# POWER_SUPPLY_PAIRED.net
KiCad netlist of a schematic drawn in Altium Designer
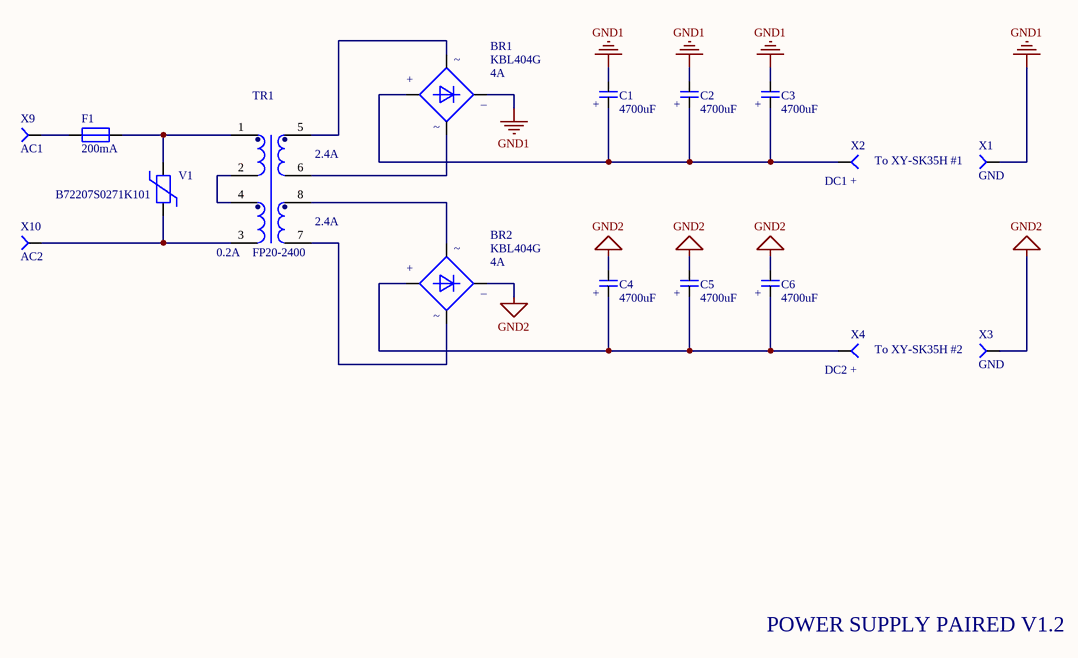
[diagram p0: POWER_SUPPLY_PAIRED.SchDoc]

(export (version "E")
  (design (tool "Eeschema 10.0.6"))
  (components
    (comp (ref "BR1")
      (value "KBL404G")
      (footprint "THT_BRIGDE_KBL404G")
      (description "THT Diode Bridge 400V 4A KBL404G TAIWAN SEMICONDUCTOR")
      (libsource (lib "THT_BRIGDE_KBL404G") (part "THT_BRIGDE_KBL404G"))
    )
    (comp (ref "BR2")
      (value "KBL404G")
      (footprint "THT_BRIGDE_KBL404G")
      (description "THT Diode Bridge 400V 4A KBL404G TAIWAN SEMICONDUCTOR")
      (libsource (lib "THT_BRIGDE_KBL404G") (part "THT_BRIGDE_KBL404G"))
    )
    (comp (ref "C1")
      (value "4700uF")
      (footprint "THT_CAP_EL_SAMXON_EKM478M1HL40RRSAP")
      (description "THT Capacitor Electrolytic 50V 4700uF Pitch 7.5mm SAMXON EKM478M1HL40RRSAP")
      (libsource (lib "THT_CAP_EL_SAMXON_EKM478M1HL40RRSAP") (part "THT_CAP_EL_SAMXON_EKM478M1HL40RRSAP"))
    )
    (comp (ref "C2")
      (value "4700uF")
      (footprint "THT_CAP_EL_SAMXON_EKM478M1HL40RRSAP")
      (description "THT Capacitor Electrolytic 50V 4700uF Pitch 7.5mm SAMXON EKM478M1HL40RRSAP")
      (libsource (lib "THT_CAP_EL_SAMXON_EKM478M1HL40RRSAP") (part "THT_CAP_EL_SAMXON_EKM478M1HL40RRSAP"))
    )
    (comp (ref "C3")
      (value "4700uF")
      (footprint "THT_CAP_EL_SAMXON_EKM478M1HL40RRSAP")
      (description "THT Capacitor Electrolytic 50V 4700uF Pitch 7.5mm SAMXON EKM478M1HL40RRSAP")
      (libsource (lib "THT_CAP_EL_SAMXON_EKM478M1HL40RRSAP") (part "THT_CAP_EL_SAMXON_EKM478M1HL40RRSAP"))
    )
    (comp (ref "C4")
      (value "4700uF")
      (footprint "THT_CAP_EL_SAMXON_EKM478M1HL40RRSAP")
      (description "THT Capacitor Electrolytic 50V 4700uF Pitch 7.5mm SAMXON EKM478M1HL40RRSAP")
      (libsource (lib "THT_CAP_EL_SAMXON_EKM478M1HL40RRSAP") (part "THT_CAP_EL_SAMXON_EKM478M1HL40RRSAP"))
    )
    (comp (ref "C5")
      (value "4700uF")
      (footprint "THT_CAP_EL_SAMXON_EKM478M1HL40RRSAP")
      (description "THT Capacitor Electrolytic 50V 4700uF Pitch 7.5mm SAMXON EKM478M1HL40RRSAP")
      (libsource (lib "THT_CAP_EL_SAMXON_EKM478M1HL40RRSAP") (part "THT_CAP_EL_SAMXON_EKM478M1HL40RRSAP"))
    )
    (comp (ref "C6")
      (value "4700uF")
      (footprint "THT_CAP_EL_SAMXON_EKM478M1HL40RRSAP")
      (description "THT Capacitor Electrolytic 50V 4700uF Pitch 7.5mm SAMXON EKM478M1HL40RRSAP")
      (libsource (lib "THT_CAP_EL_SAMXON_EKM478M1HL40RRSAP") (part "THT_CAP_EL_SAMXON_EKM478M1HL40RRSAP"))
    )
    (comp (ref "F1")
      (value "200mA")
      (footprint "THT_FUSE-MICRO_MTS0200A")
      (description "THT Fuse Slow Blow Micro Fuse, 250V/200mA REOMAX")
      (libsource (lib "THT_FUSE-MICRO_MTS0200A") (part "THT_FUSE-MICRO_MTS0200A"))
    )
    (comp (ref "TR1")
      (value "FP20-2400")
      (footprint "THT_TRFMR_FP20-2400_TRIADMAG")
      (description "THT Power Transformer 48VA Secondary=2.4A  Primary=230 VAC Secondary=20V FP20-2400 TRIAD MAGNETICS")
      (libsource (lib "THT_TRFMR_FP20-2400_TRIADMAG") (part "THT_TRFMR_FP20-2400_TRIADMAG"))
    )
    (comp (ref "V1")
      (value "B72207S0271K101")
      (footprint "THT_VAR_B72207S0271K101")
      (description "THT Varistor 275V 1200A B72207S0271K101 EPCOS(TDK)")
      (libsource (lib "THT_VAR_B72207S0271K101") (part "THT_VAR_B72207S0271K101"))
    )
    (comp (ref "X1")
      (value "GND")
      (footprint "THT_TERMINAL-PCB_L-KLS8-01128-PC-250")
      (description "THT Terminal Tab PCB L-KLS8-01128-PC-250 KLS ELECTRONIC")
      (libsource (lib "THT_TERMINAL-PCB_L-KLS8-01128-PC-250") (part "THT_TERMINAL-PCB_L-KLS8-01128-PC-250"))
    )
    (comp (ref "X2")
      (value "DC1 +")
      (footprint "THT_TERMINAL-PCB_L-KLS8-01128-PC-250")
      (description "THT Terminal Tab PCB L-KLS8-01128-PC-250 KLS ELECTRONIC")
      (libsource (lib "THT_TERMINAL-PCB_L-KLS8-01128-PC-250") (part "THT_TERMINAL-PCB_L-KLS8-01128-PC-250"))
    )
    (comp (ref "X3")
      (value "GND")
      (footprint "THT_TERMINAL-PCB_L-KLS8-01128-PC-250")
      (description "THT Terminal Tab PCB L-KLS8-01128-PC-250 KLS ELECTRONIC")
      (libsource (lib "THT_TERMINAL-PCB_L-KLS8-01128-PC-250") (part "THT_TERMINAL-PCB_L-KLS8-01128-PC-250"))
    )
    (comp (ref "X4")
      (value "DC2 +")
      (footprint "THT_TERMINAL-PCB_L-KLS8-01128-PC-250")
      (description "THT Terminal Tab PCB L-KLS8-01128-PC-250 KLS ELECTRONIC")
      (libsource (lib "THT_TERMINAL-PCB_L-KLS8-01128-PC-250") (part "THT_TERMINAL-PCB_L-KLS8-01128-PC-250"))
    )
    (comp (ref "X9")
      (value "AC1")
      (footprint "THT_TERMINAL-PCB_L-KLS8-01128-PC-250")
      (description "THT Terminal Tab PCB L-KLS8-01128-PC-250 KLS ELECTRONIC")
      (libsource (lib "THT_TERMINAL-PCB_L-KLS8-01128-PC-250") (part "THT_TERMINAL-PCB_L-KLS8-01128-PC-250"))
    )
    (comp (ref "X10")
      (value "AC2")
      (footprint "THT_TERMINAL-PCB_L-KLS8-01128-PC-250")
      (description "THT Terminal Tab PCB L-KLS8-01128-PC-250 KLS ELECTRONIC")
      (libsource (lib "THT_TERMINAL-PCB_L-KLS8-01128-PC-250") (part "THT_TERMINAL-PCB_L-KLS8-01128-PC-250"))
    )
  )
  (nets
    (net (code "1") (name "GND1") (class "Default")
      (node (ref "BR1") (pin "4") (pinfunction "-_4") (pintype "passive"))
      (node (ref "C1") (pin "2") (pinfunction "2_2") (pintype "passive"))
      (node (ref "C2") (pin "2") (pinfunction "2_2") (pintype "passive"))
      (node (ref "C3") (pin "2") (pinfunction "2_2") (pintype "passive"))
      (node (ref "X1") (pin "1") (pintype "power_in"))
    )
    (net (code "2") (name "GND2") (class "Default")
      (node (ref "BR2") (pin "4") (pinfunction "-_4") (pintype "passive"))
      (node (ref "C4") (pin "2") (pinfunction "2_2") (pintype "passive"))
      (node (ref "C5") (pin "2") (pinfunction "2_2") (pintype "passive"))
      (node (ref "C6") (pin "2") (pinfunction "2_2") (pintype "passive"))
      (node (ref "X3") (pin "1") (pintype "power_in"))
    )
    (net (code "3") (name "Net-(BR1-+)") (class "Default")
      (node (ref "BR1") (pin "1") (pinfunction "+_1") (pintype "passive"))
      (node (ref "C1") (pin "1") (pinfunction "1_1") (pintype "passive"))
      (node (ref "C2") (pin "1") (pinfunction "1_1") (pintype "passive"))
      (node (ref "C3") (pin "1") (pinfunction "1_1") (pintype "passive"))
      (node (ref "X2") (pin "1") (pintype "power_in"))
    )
    (net (code "4") (name "Net-(BR1-~-Pad2)") (class "Default")
      (node (ref "BR1") (pin "2") (pinfunction "~_2") (pintype "passive"))
      (node (ref "TR1") (pin "5") (pinfunction "5_5") (pintype "passive"))
    )
    (net (code "5") (name "Net-(BR1-~-Pad3)") (class "Default")
      (node (ref "BR1") (pin "3") (pinfunction "~_3") (pintype "passive"))
      (node (ref "TR1") (pin "6") (pinfunction "6_6") (pintype "passive"))
    )
    (net (code "6") (name "Net-(BR2-+)") (class "Default")
      (node (ref "BR2") (pin "1") (pinfunction "+_1") (pintype "passive"))
      (node (ref "C4") (pin "1") (pinfunction "1_1") (pintype "passive"))
      (node (ref "C5") (pin "1") (pinfunction "1_1") (pintype "passive"))
      (node (ref "C6") (pin "1") (pinfunction "1_1") (pintype "passive"))
      (node (ref "X4") (pin "1") (pintype "power_in"))
    )
    (net (code "7") (name "Net-(BR2-~-Pad2)") (class "Default")
      (node (ref "BR2") (pin "2") (pinfunction "~_2") (pintype "passive"))
      (node (ref "TR1") (pin "8") (pinfunction "8_8") (pintype "passive"))
    )
    (net (code "8") (name "Net-(BR2-~-Pad3)") (class "Default")
      (node (ref "BR2") (pin "3") (pinfunction "~_3") (pintype "passive"))
      (node (ref "TR1") (pin "7") (pinfunction "7_7") (pintype "passive"))
    )
    (net (code "9") (name "Net-(F1-Pad1)") (class "Default")
      (node (ref "F1") (pin "1") (pinfunction "1_1") (pintype "passive"))
      (node (ref "X9") (pin "1") (pintype "power_in"))
    )
    (net (code "10") (name "Net-(F1-Pad2)") (class "Default")
      (node (ref "F1") (pin "2") (pinfunction "2_2") (pintype "passive"))
      (node (ref "TR1") (pin "1") (pinfunction "1_1") (pintype "passive"))
      (node (ref "V1") (pin "2") (pinfunction "2_2") (pintype "passive"))
    )
    (net (code "11") (name "Net-(TR1-Pad2)") (class "Default")
      (node (ref "TR1") (pin "2") (pinfunction "2_2") (pintype "passive"))
      (node (ref "TR1") (pin "4") (pinfunction "4_4") (pintype "passive"))
    )
    (net (code "12") (name "Net-(TR1-Pad3)") (class "Default")
      (node (ref "TR1") (pin "3") (pinfunction "3_3") (pintype "passive"))
      (node (ref "V1") (pin "1") (pinfunction "1_1") (pintype "passive"))
      (node (ref "X10") (pin "1") (pintype "power_in"))
    )
  )
)
